# SCH_LED-Project-Erfan_2025-10-19.net
KiCad netlist of a schematic drawn in EasyEDA
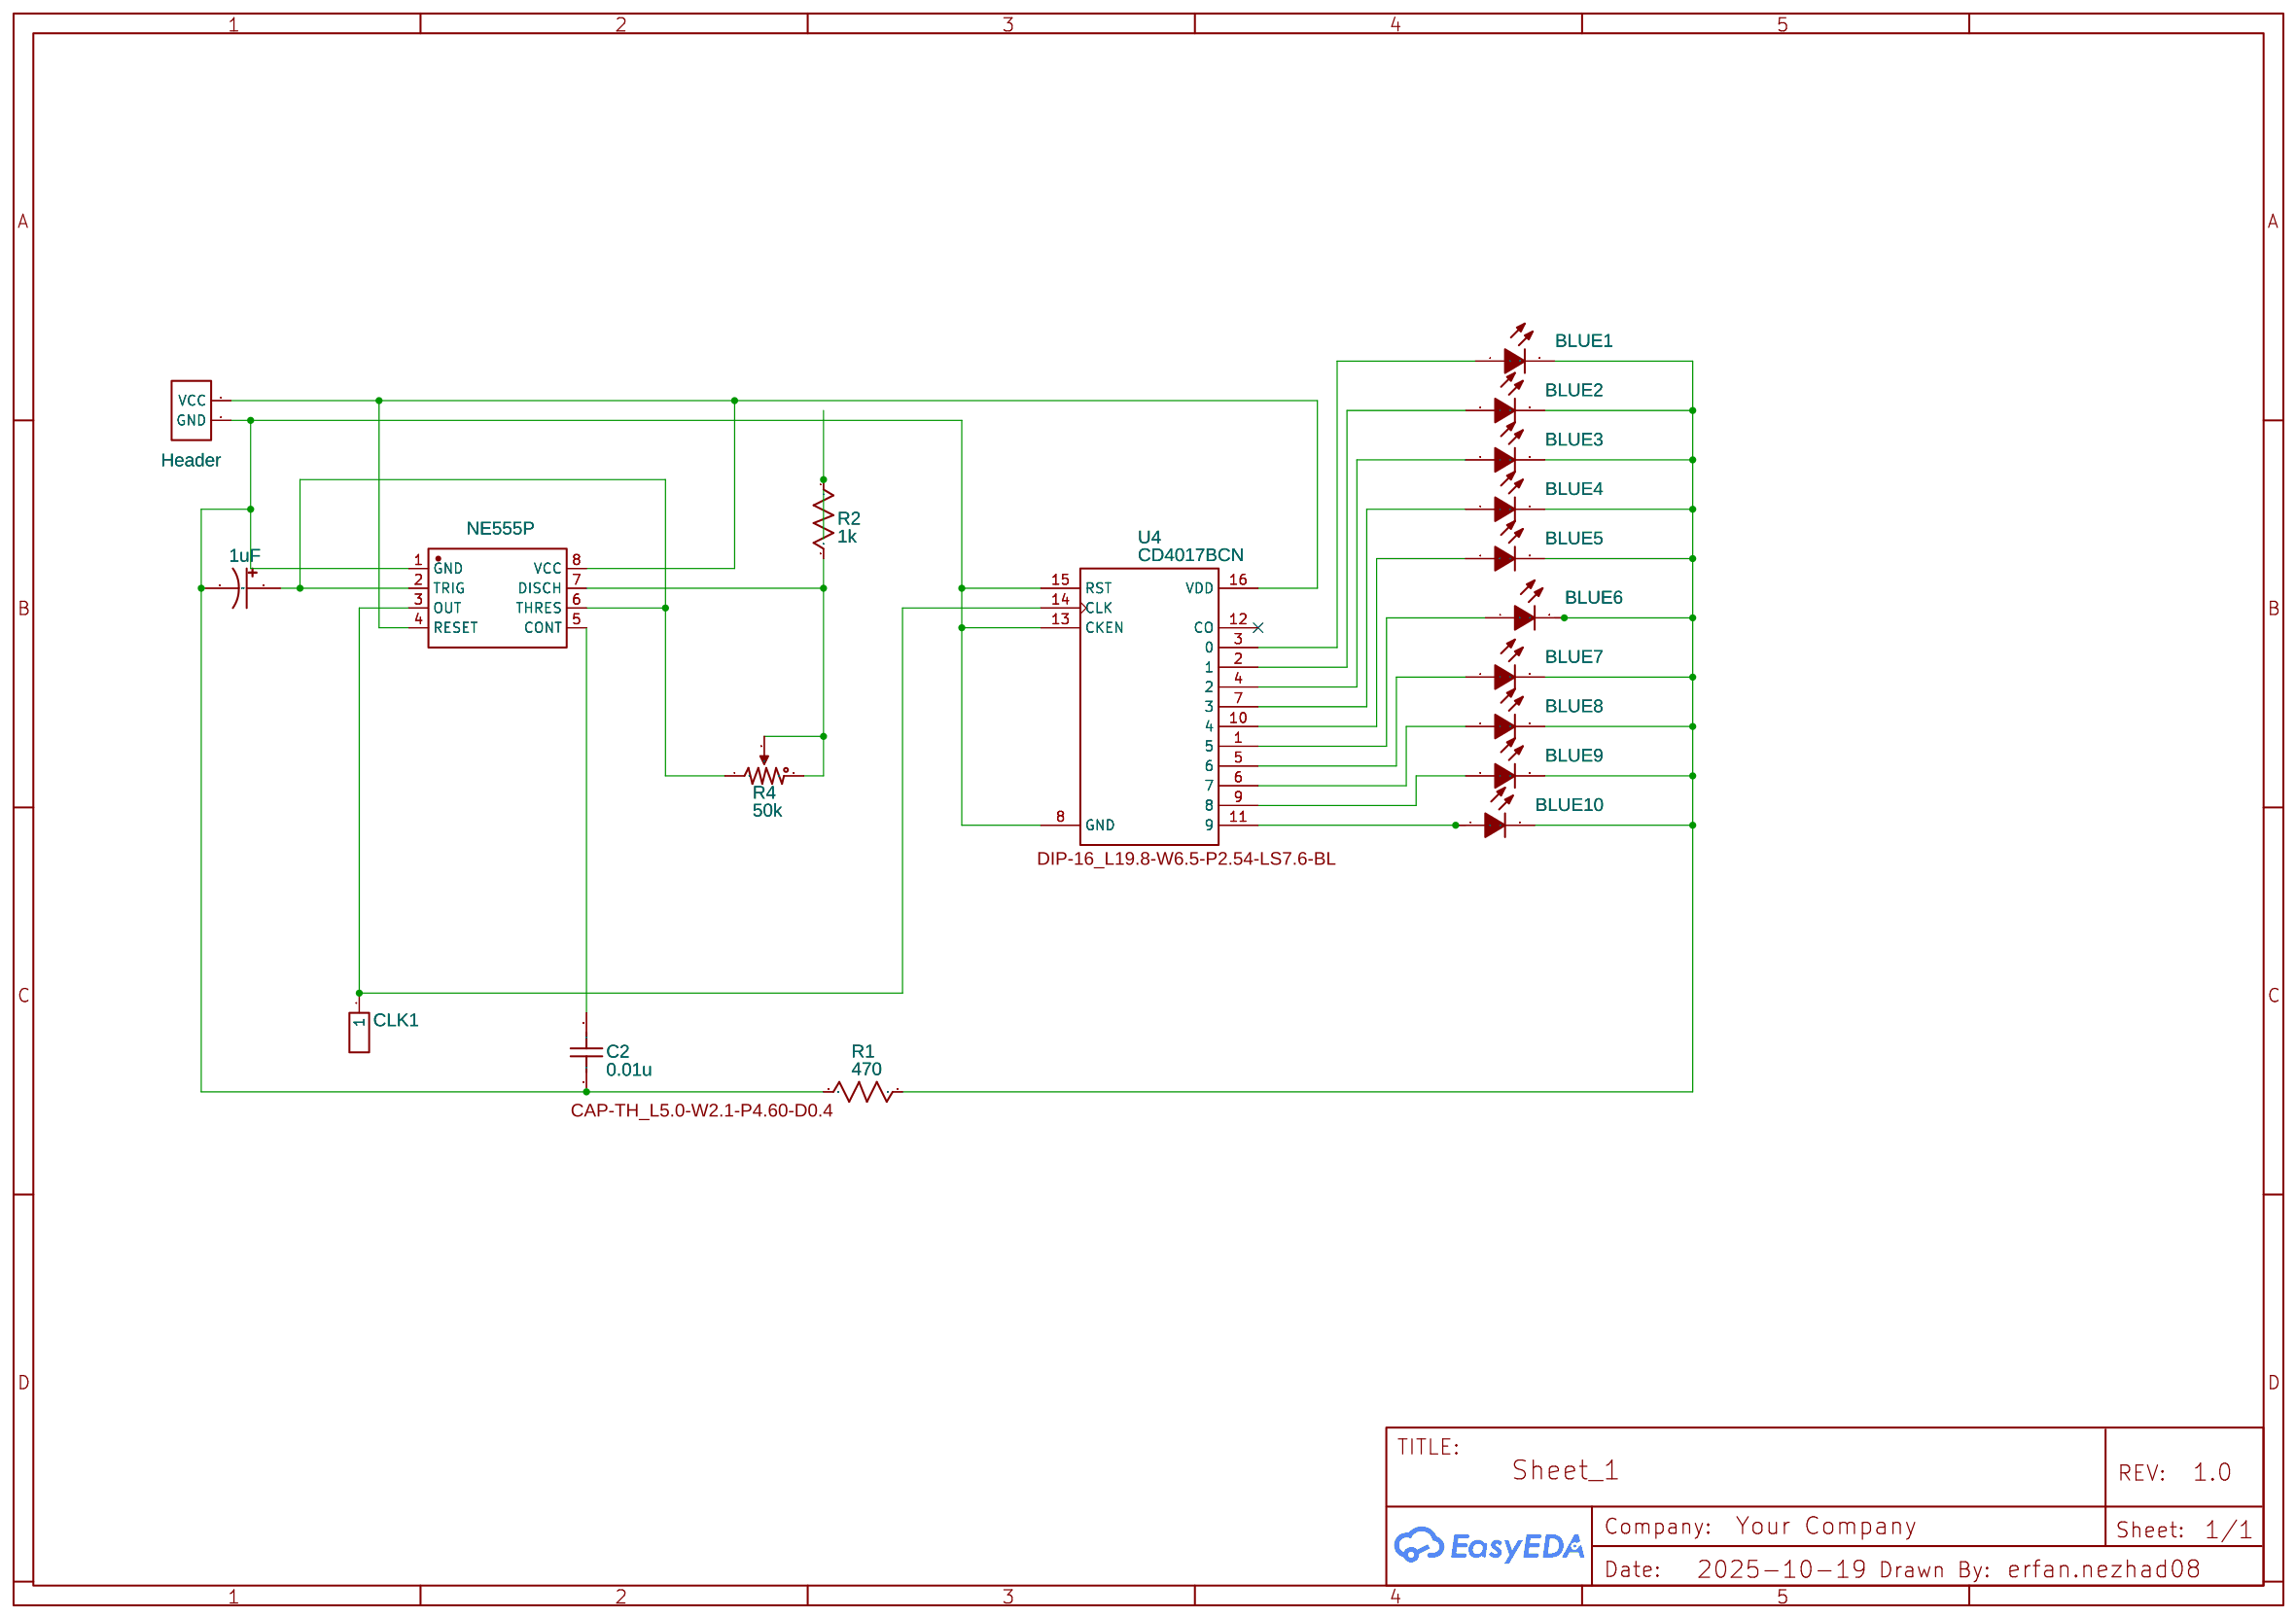
[diagram p0: schematic sheet]

(export (version "E")
  (design (tool "Eeschema 10.0.6"))
  (components
    (comp (ref "BLUE1") (value "LED_5MM") (libsource (lib "") (part "LED_5MM")))
    (comp (ref "BLUE2") (value "LED_5MM") (libsource (lib "") (part "LED_5MM")))
    (comp (ref "BLUE3") (value "LED_5MM") (libsource (lib "") (part "LED_5MM")))
    (comp (ref "BLUE4") (value "LED_5MM") (libsource (lib "") (part "LED_5MM")))
    (comp (ref "BLUE5") (value "LED_5MM") (libsource (lib "") (part "LED_5MM")))
    (comp (ref "BLUE6") (value "LED_5MM") (libsource (lib "") (part "LED_5MM")))
    (comp (ref "BLUE7") (value "LED_5MM") (libsource (lib "") (part "LED_5MM")))
    (comp (ref "BLUE8") (value "LED_5MM") (libsource (lib "") (part "LED_5MM")))
    (comp (ref "BLUE9") (value "LED_5MM") (libsource (lib "") (part "LED_5MM")))
    (comp (ref "BLUE10") (value "LED_5MM") (libsource (lib "") (part "LED_5MM")))
    (comp (ref "C1")
      (value "1uF")
      (fields (field (name "Manufacturer Part") "UVZ1H010MDD") (field (name "Manufacturer") "Nichicon(尼吉康)"))
      (libsource (lib "") (part "UVZ1H010MDD"))
    )
    (comp (ref "C2") (value "0.01u") (libsource (lib "") (part "C_0603_US")))
    (comp (ref "CLK1")
      (value "C81276")
      (fields
        (field (name "Manufacturer Part") "2.54-1*1P针")
        (field (name "Manufacturer") "BOOMELE(Boom Precision Elec)")
      )
      (libsource (lib "") (part "Header-Male-2.54_1x1"))
    )
    (comp (ref "H1") (value "Header") (libsource (lib "") (part "HEADER-FEMALE-2.54_1X2")))
    (comp (ref "R1")
      (value "470")
      (fields (field (name "Manufacturer Part") "?"))
      (libsource (lib "") (part "Resistor"))
    )
    (comp (ref "R2")
      (value "1k")
      (fields (field (name "Manufacturer Part") "?"))
      (libsource (lib "") (part "Resistor_1"))
    )
    (comp (ref "R4")
      (value "50k")
      (fields (field (name "Manufacturer Part") "?"))
      (libsource (lib "") (part "Potentiometer"))
    )
    (comp (ref "U2")
      (value "NE555P")
      (fields (field (name "Manufacturer") "TI(德州仪器)"))
      (libsource (lib "") (part "NE555P"))
    )
    (comp (ref "U4") (value "CD4017BCN") (libsource (lib "") (part "CD4017BCN")))
  )
  (nets
    (net (code "1") (name "Net-(BLUE1-A)") (class "Default")
      (node (ref "BLUE1") (pin "1") (pinfunction "A_1") (pintype "input"))
      (node (ref "U4") (pin "3") (pinfunction "0_3") (pintype "output"))
    )
    (net (code "2") (name "Net-(BLUE1-K)") (class "Default")
      (node (ref "BLUE1") (pin "2") (pinfunction "K_2") (pintype "input"))
      (node (ref "BLUE10") (pin "2") (pinfunction "K_2") (pintype "input"))
      (node (ref "BLUE2") (pin "2") (pinfunction "K_2") (pintype "input"))
      (node (ref "BLUE3") (pin "2") (pinfunction "K_2") (pintype "input"))
      (node (ref "BLUE4") (pin "2") (pinfunction "K_2") (pintype "input"))
      (node (ref "BLUE5") (pin "2") (pinfunction "K_2") (pintype "input"))
      (node (ref "BLUE6") (pin "2") (pinfunction "K_2") (pintype "input"))
      (node (ref "BLUE7") (pin "2") (pinfunction "K_2") (pintype "input"))
      (node (ref "BLUE8") (pin "2") (pinfunction "K_2") (pintype "input"))
      (node (ref "BLUE9") (pin "2") (pinfunction "K_2") (pintype "input"))
      (node (ref "R1") (pin "1") (pinfunction "1_1") (pintype "unspecified"))
    )
    (net (code "3") (name "Net-(BLUE2-A)") (class "Default")
      (node (ref "BLUE2") (pin "1") (pinfunction "A_1") (pintype "input"))
      (node (ref "U4") (pin "2") (pinfunction "1_2") (pintype "output"))
    )
    (net (code "4") (name "Net-(BLUE3-A)") (class "Default")
      (node (ref "BLUE3") (pin "1") (pinfunction "A_1") (pintype "input"))
      (node (ref "U4") (pin "4") (pinfunction "2_4") (pintype "output"))
    )
    (net (code "5") (name "Net-(BLUE4-A)") (class "Default")
      (node (ref "BLUE4") (pin "1") (pinfunction "A_1") (pintype "input"))
      (node (ref "U4") (pin "7") (pinfunction "3_7") (pintype "output"))
    )
    (net (code "6") (name "Net-(BLUE5-A)") (class "Default")
      (node (ref "BLUE5") (pin "1") (pinfunction "A_1") (pintype "input"))
      (node (ref "U4") (pin "10") (pinfunction "4_10") (pintype "output"))
    )
    (net (code "7") (name "Net-(BLUE6-A)") (class "Default")
      (node (ref "BLUE6") (pin "1") (pinfunction "A_1") (pintype "input"))
      (node (ref "U4") (pin "1") (pinfunction "5_1") (pintype "output"))
    )
    (net (code "8") (name "Net-(BLUE7-A)") (class "Default")
      (node (ref "BLUE7") (pin "1") (pinfunction "A_1") (pintype "input"))
      (node (ref "U4") (pin "5") (pinfunction "6_5") (pintype "output"))
    )
    (net (code "9") (name "Net-(BLUE8-A)") (class "Default")
      (node (ref "BLUE8") (pin "1") (pinfunction "A_1") (pintype "input"))
      (node (ref "U4") (pin "6") (pinfunction "7_6") (pintype "output"))
    )
    (net (code "10") (name "Net-(BLUE9-A)") (class "Default")
      (node (ref "BLUE9") (pin "1") (pinfunction "A_1") (pintype "input"))
      (node (ref "U4") (pin "9") (pinfunction "8_9") (pintype "output"))
    )
    (net (code "11") (name "Net-(BLUE10-A)") (class "Default")
      (node (ref "BLUE10") (pin "1") (pinfunction "A_1") (pintype "input"))
      (node (ref "U4") (pin "11") (pinfunction "9_11") (pintype "output"))
    )
    (net (code "12") (name "Net-(H1-GND)") (class "Default")
      (node (ref "C1") (pin "2") (pinfunction "2_2") (pintype "unspecified"))
      (node (ref "C2") (pin "1") (pinfunction "1_1") (pintype "unspecified"))
      (node (ref "H1") (pin "2") (pinfunction "GND_2") (pintype "unspecified"))
      (node (ref "R1") (pin "2") (pinfunction "2_2") (pintype "unspecified"))
      (node (ref "U2") (pin "1") (pinfunction "GND_1") (pintype "unspecified"))
      (node (ref "U4") (pin "13") (pinfunction "CKEN_13") (pintype "unspecified"))
      (node (ref "U4") (pin "15") (pinfunction "RST_15") (pintype "unspecified"))
      (node (ref "U4") (pin "8") (pinfunction "GND_8") (pintype "passive"))
    )
    (net (code "13") (name "Net-(H1-VCC)") (class "Default")
      (node (ref "H1") (pin "1") (pinfunction "VCC_1") (pintype "unspecified"))
      (node (ref "U2") (pin "4") (pinfunction "RESET_4") (pintype "unspecified"))
      (node (ref "U2") (pin "8") (pinfunction "VCC_8") (pintype "unspecified"))
      (node (ref "U4") (pin "16") (pinfunction "VDD_16") (pintype "passive"))
    )
    (net (code "14") (name "Net-(R4-2)") (class "Default")
      (node (ref "R2") (pin "2") (pinfunction "2_2") (pintype "unspecified"))
      (node (ref "R4") (pin "2") (pinfunction "3_2") (pintype "unspecified"))
      (node (ref "R4") (pin "3") (pinfunction "2_3") (pintype "unspecified"))
      (node (ref "U2") (pin "7") (pinfunction "DISCH_7") (pintype "unspecified"))
    )
    (net (code "15") (name "Net-(U2-CONT)") (class "Default")
      (node (ref "C2") (pin "2") (pinfunction "2_2") (pintype "unspecified"))
      (node (ref "U2") (pin "5") (pinfunction "CONT_5") (pintype "unspecified"))
    )
    (net (code "16") (name "Net-(U2-OUT)") (class "Default")
      (node (ref "CLK1") (pin "1") (pinfunction "1_1") (pintype "unspecified"))
      (node (ref "U2") (pin "3") (pinfunction "OUT_3") (pintype "unspecified"))
      (node (ref "U4") (pin "14") (pinfunction "CLK_14") (pintype "unspecified"))
    )
    (net (code "17") (name "Net-(U2-THRES)") (class "Default")
      (node (ref "C1") (pin "1") (pinfunction "1_1") (pintype "unspecified"))
      (node (ref "R4") (pin "1") (pinfunction "1_1") (pintype "unspecified"))
      (node (ref "U2") (pin "2") (pinfunction "TRIG_2") (pintype "unspecified"))
      (node (ref "U2") (pin "6") (pinfunction "THRES_6") (pintype "unspecified"))
    )
    (net (code "18") (name "unconnected-(R2-Pad1)") (class "Default")
      (node (ref "R2") (pin "1") (pinfunction "1_1") (pintype "unspecified"))
    )
    (net (code "19") (name "unconnected-(U4-CO-Pad12)") (class "Default")
      (node (ref "U4") (pin "12") (pinfunction "CO_12") (pintype "output+no_connect"))
    )
  )
)
